# shield2.net
KiCad netlist of a schematic drawn in EAGLE
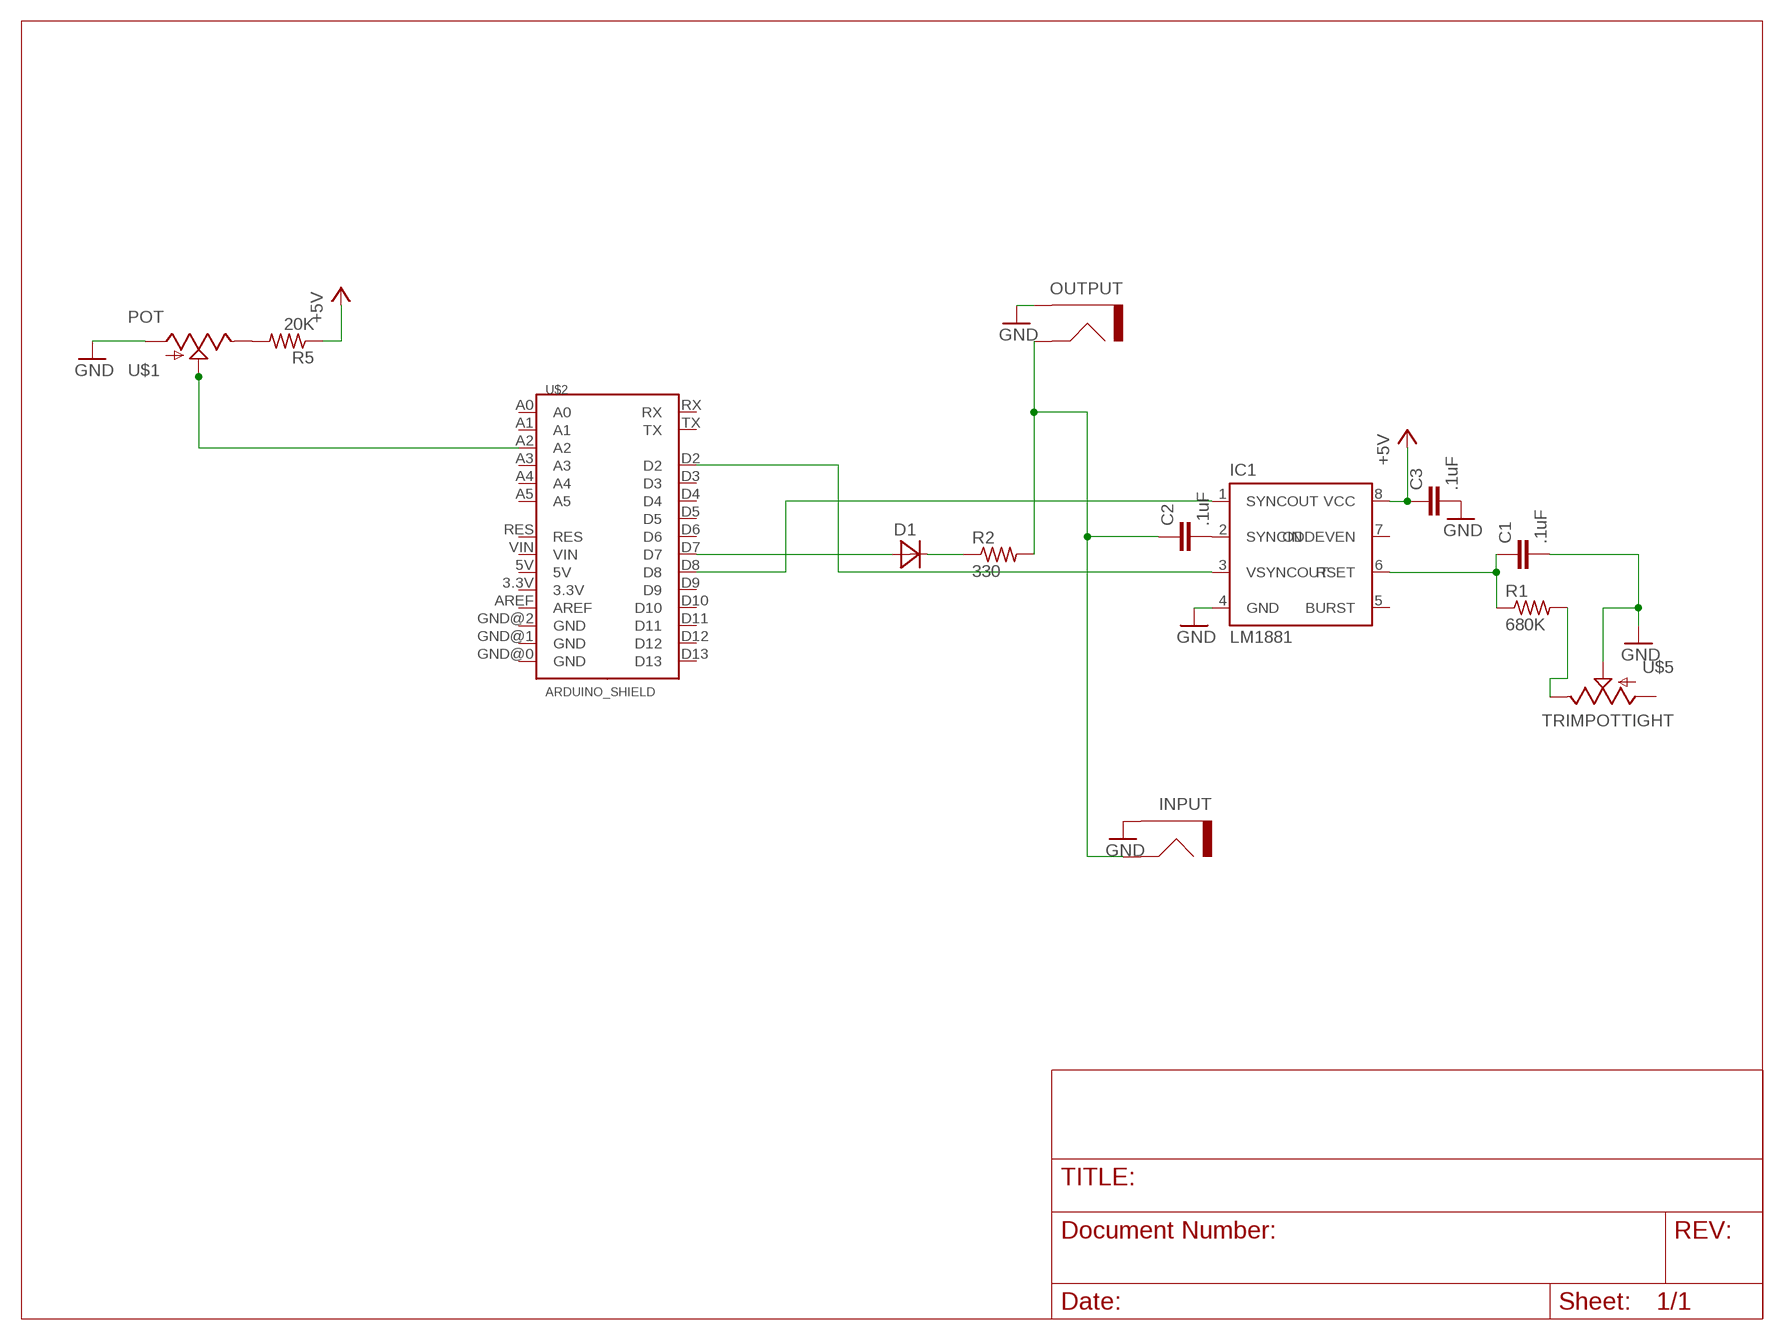
[diagram p0: schematic, sheet 1]

(export (version "E")
  (design (tool "Eeschema 10.0.6"))
  (components
    (comp (ref "C1")
      (value ".1uF")
      (footprint "eagle-import:CAP-CERAMIC-SMALL")
      (libsource (lib "eagle-import") (part "CAPSMALL"))
    )
    (comp (ref "C2")
      (value ".1uF")
      (footprint "eagle-import:CAP-CERAMIC-SMALL")
      (libsource (lib "eagle-import") (part "CAPSMALL"))
    )
    (comp (ref "C3")
      (value ".1uF")
      (footprint "eagle-import:CAP-CERAMIC-SMALL")
      (libsource (lib "eagle-import") (part "CAPSMALL"))
    )
    (comp (ref "D1")
      (value "1N4148")
      (footprint "eagle-import:D35-10")
      (libsource (lib "eagle-import") (part "1N4148"))
    )
    (comp (ref "IC1")
      (value "LM1881")
      (footprint "eagle-import:DIL08")
      (libsource (lib "eagle-import") (part "LM1881"))
    )
    (comp (ref "INPUT")
      (value "RCAJACK")
      (footprint "eagle-import:RCA")
      (libsource (lib "eagle-import") (part "RCAJACK"))
    )
    (comp (ref "OUTPUT")
      (value "RCAJACK")
      (footprint "eagle-import:RCA")
      (libsource (lib "eagle-import") (part "RCAJACK"))
    )
    (comp (ref "R1")
      (value "680K")
      (footprint "eagle-import:0207_10")
      (libsource (lib "eagle-import") (part "R-US"))
    )
    (comp (ref "R2")
      (value "330")
      (footprint "eagle-import:0207_10")
      (libsource (lib "eagle-import") (part "R-US"))
    )
    (comp (ref "R5")
      (value "20K")
      (footprint "eagle-import:0207_10")
      (libsource (lib "eagle-import") (part "R-US"))
    )
    (comp (ref "U$1")
      (value "POT")
      (footprint "eagle-import:TRIMMERPOT")
      (libsource (lib "eagle-import") (part "POT"))
    )
    (comp (ref "U$2")
      (value "ARDUINO_SHIELD")
      (footprint "eagle-import:DUEMILANOVE_SHIELD")
      (libsource (lib "eagle-import") (part "ARDUINO_SHIELD"))
    )
    (comp (ref "U$5")
      (value "TRIMPOTTIGHT")
      (footprint "eagle-import:TRIM_POT_TIGHT")
      (libsource (lib "eagle-import") (part "TRIMPOTTIGHT"))
    )
  )
  (nets
    (net (code "1") (name "+5V") (class "Default")
      (node (ref "C3") (pin "1") (pinfunction "1_1") (pintype "passive"))
      (node (ref "IC1") (pin "8") (pinfunction "VCC_8") (pintype "power_in"))
      (node (ref "R5") (pin "1") (pinfunction "1_1") (pintype "passive"))
    )
    (net (code "2") (name "GND") (class "Default")
      (node (ref "C1") (pin "2") (pinfunction "2_2") (pintype "passive"))
      (node (ref "C3") (pin "2") (pinfunction "2_2") (pintype "passive"))
      (node (ref "IC1") (pin "4") (pinfunction "GND_4") (pintype "power_in"))
      (node (ref "INPUT") (pin "BARREL") (pinfunction "GND_BARREL") (pintype "bidirectional"))
      (node (ref "OUTPUT") (pin "BARREL") (pinfunction "GND_BARREL") (pintype "bidirectional"))
      (node (ref "U$1") (pin "1") (pinfunction "1_1") (pintype "passive"))
      (node (ref "U$5") (pin "2") (pinfunction "2_2") (pintype "passive"))
    )
    (net (code "3") (name "Net-(D1-PadA)") (class "Default")
      (node (ref "D1") (pin "A") (pinfunction "A_A") (pintype "passive"))
      (node (ref "U$2") (pin "D7") (pinfunction "D7_D7") (pintype "bidirectional"))
    )
    (net (code "4") (name "Net-(D1-PadC)") (class "Default")
      (node (ref "D1") (pin "C") (pinfunction "C_C") (pintype "passive"))
      (node (ref "R2") (pin "1") (pinfunction "1_1") (pintype "passive"))
    )
    (net (code "5") (name "Net-(IC1-RSET)") (class "Default")
      (node (ref "C1") (pin "1") (pinfunction "1_1") (pintype "passive"))
      (node (ref "IC1") (pin "6") (pinfunction "RSET_6") (pintype "output"))
      (node (ref "R1") (pin "1") (pinfunction "1_1") (pintype "passive"))
    )
    (net (code "6") (name "Net-(IC1-SYNCIN)") (class "Default")
      (node (ref "C2") (pin "2") (pinfunction "2_2") (pintype "passive"))
      (node (ref "IC1") (pin "2") (pinfunction "SYNCIN_2") (pintype "input"))
    )
    (net (code "7") (name "Net-(IC1-SYNCOUT)") (class "Default")
      (node (ref "IC1") (pin "1") (pinfunction "SYNCOUT_1") (pintype "output"))
      (node (ref "U$2") (pin "D8") (pinfunction "D8_D8") (pintype "bidirectional"))
    )
    (net (code "8") (name "Net-(IC1-VSYNCOUT)") (class "Default")
      (node (ref "IC1") (pin "3") (pinfunction "VSYNCOUT_3") (pintype "output"))
      (node (ref "U$2") (pin "D2") (pinfunction "D2_D2") (pintype "bidirectional"))
    )
    (net (code "9") (name "Net-(INPUT-SIGNAL)") (class "Default")
      (node (ref "C2") (pin "1") (pinfunction "1_1") (pintype "passive"))
      (node (ref "INPUT") (pin "P$2") (pinfunction "SIGNAL_P$2") (pintype "bidirectional"))
      (node (ref "OUTPUT") (pin "P$2") (pinfunction "SIGNAL_P$2") (pintype "bidirectional"))
      (node (ref "R2") (pin "2") (pinfunction "2_2") (pintype "passive"))
    )
    (net (code "10") (name "Net-(R1-Pad2)") (class "Default")
      (node (ref "R1") (pin "2") (pinfunction "2_2") (pintype "passive"))
      (node (ref "U$5") (pin "3") (pinfunction "3_3") (pintype "passive"))
    )
    (net (code "11") (name "Net-(R5-Pad2)") (class "Default")
      (node (ref "R5") (pin "2") (pinfunction "2_2") (pintype "passive"))
      (node (ref "U$1") (pin "3") (pinfunction "3_3") (pintype "passive"))
    )
    (net (code "12") (name "Net-(U$1-WIPER-Pad2)") (class "Default")
      (node (ref "U$1") (pin "2") (pinfunction "WIPER_2") (pintype "passive"))
      (node (ref "U$1") (pin "4") (pinfunction "WIPER_4") (pintype "passive"))
      (node (ref "U$2") (pin "A2") (pinfunction "A2_A2") (pintype "bidirectional"))
    )
    (net (code "13") (name "unconnected-(IC1-BURST-Pad5)") (class "Default")
      (node (ref "IC1") (pin "5") (pinfunction "BURST_5") (pintype "output"))
    )
    (net (code "14") (name "unconnected-(IC1-ODDEVEN-Pad7)") (class "Default")
      (node (ref "IC1") (pin "7") (pinfunction "ODDEVEN_7") (pintype "output"))
    )
    (net (code "15") (name "unconnected-(U$2-GND-PadGND@0)") (class "Default")
      (node (ref "U$2") (pin "GND@0") (pinfunction "GND_GND@0") (pintype "bidirectional"))
    )
    (net (code "16") (name "unconnected-(U$2-GND-PadGND@1)") (class "Default")
      (node (ref "U$2") (pin "GND@1") (pinfunction "GND_GND@1") (pintype "bidirectional"))
    )
    (net (code "17") (name "unconnected-(U$2-GND-PadGND@2)") (class "Default")
      (node (ref "U$2") (pin "GND@2") (pinfunction "GND_GND@2") (pintype "bidirectional"))
    )
    (net (code "18") (name "unconnected-(U$2-Pad3.3V)") (class "Default")
      (node (ref "U$2") (pin "3.3V") (pinfunction "3.3V_3.3V") (pintype "bidirectional"))
    )
    (net (code "19") (name "unconnected-(U$2-Pad5V)") (class "Default")
      (node (ref "U$2") (pin "5V") (pinfunction "5V_5V") (pintype "bidirectional"))
    )
    (net (code "20") (name "unconnected-(U$2-PadA0)") (class "Default")
      (node (ref "U$2") (pin "A0") (pinfunction "A0_A0") (pintype "bidirectional"))
    )
    (net (code "21") (name "unconnected-(U$2-PadA1)") (class "Default")
      (node (ref "U$2") (pin "A1") (pinfunction "A1_A1") (pintype "bidirectional"))
    )
    (net (code "22") (name "unconnected-(U$2-PadA3)") (class "Default")
      (node (ref "U$2") (pin "A3") (pinfunction "A3_A3") (pintype "bidirectional"))
    )
    (net (code "23") (name "unconnected-(U$2-PadA4)") (class "Default")
      (node (ref "U$2") (pin "A4") (pinfunction "A4_A4") (pintype "bidirectional"))
    )
    (net (code "24") (name "unconnected-(U$2-PadA5)") (class "Default")
      (node (ref "U$2") (pin "A5") (pinfunction "A5_A5") (pintype "bidirectional"))
    )
    (net (code "25") (name "unconnected-(U$2-PadAREF)") (class "Default")
      (node (ref "U$2") (pin "AREF") (pinfunction "AREF_AREF") (pintype "bidirectional"))
    )
    (net (code "26") (name "unconnected-(U$2-PadD3)") (class "Default")
      (node (ref "U$2") (pin "D3") (pinfunction "D3_D3") (pintype "bidirectional"))
    )
    (net (code "27") (name "unconnected-(U$2-PadD4)") (class "Default")
      (node (ref "U$2") (pin "D4") (pinfunction "D4_D4") (pintype "bidirectional"))
    )
    (net (code "28") (name "unconnected-(U$2-PadD5)") (class "Default")
      (node (ref "U$2") (pin "D5") (pinfunction "D5_D5") (pintype "bidirectional"))
    )
    (net (code "29") (name "unconnected-(U$2-PadD6)") (class "Default")
      (node (ref "U$2") (pin "D6") (pinfunction "D6_D6") (pintype "bidirectional"))
    )
    (net (code "30") (name "unconnected-(U$2-PadD9)") (class "Default")
      (node (ref "U$2") (pin "D9") (pinfunction "D9_D9") (pintype "bidirectional"))
    )
    (net (code "31") (name "unconnected-(U$2-PadD10)") (class "Default")
      (node (ref "U$2") (pin "D10") (pinfunction "D10_D10") (pintype "bidirectional"))
    )
    (net (code "32") (name "unconnected-(U$2-PadD11)") (class "Default")
      (node (ref "U$2") (pin "D11") (pinfunction "D11_D11") (pintype "bidirectional"))
    )
    (net (code "33") (name "unconnected-(U$2-PadD12)") (class "Default")
      (node (ref "U$2") (pin "D12") (pinfunction "D12_D12") (pintype "bidirectional"))
    )
    (net (code "34") (name "unconnected-(U$2-PadD13)") (class "Default")
      (node (ref "U$2") (pin "D13") (pinfunction "D13_D13") (pintype "bidirectional"))
    )
    (net (code "35") (name "unconnected-(U$2-PadRES)") (class "Default")
      (node (ref "U$2") (pin "RES") (pinfunction "RES_RES") (pintype "bidirectional"))
    )
    (net (code "36") (name "unconnected-(U$2-PadRX)") (class "Default")
      (node (ref "U$2") (pin "RX") (pinfunction "RX_RX") (pintype "bidirectional"))
    )
    (net (code "37") (name "unconnected-(U$2-PadTX)") (class "Default")
      (node (ref "U$2") (pin "TX") (pinfunction "TX_TX") (pintype "bidirectional"))
    )
    (net (code "38") (name "unconnected-(U$2-PadVIN)") (class "Default")
      (node (ref "U$2") (pin "VIN") (pinfunction "VIN_VIN") (pintype "bidirectional"))
    )
    (net (code "39") (name "unconnected-(U$5-Pad1)") (class "Default")
      (node (ref "U$5") (pin "1") (pinfunction "1_1") (pintype "passive"))
    )
  )
)
